# Memory.net
KiCad netlist of a schematic drawn in Altium Designer
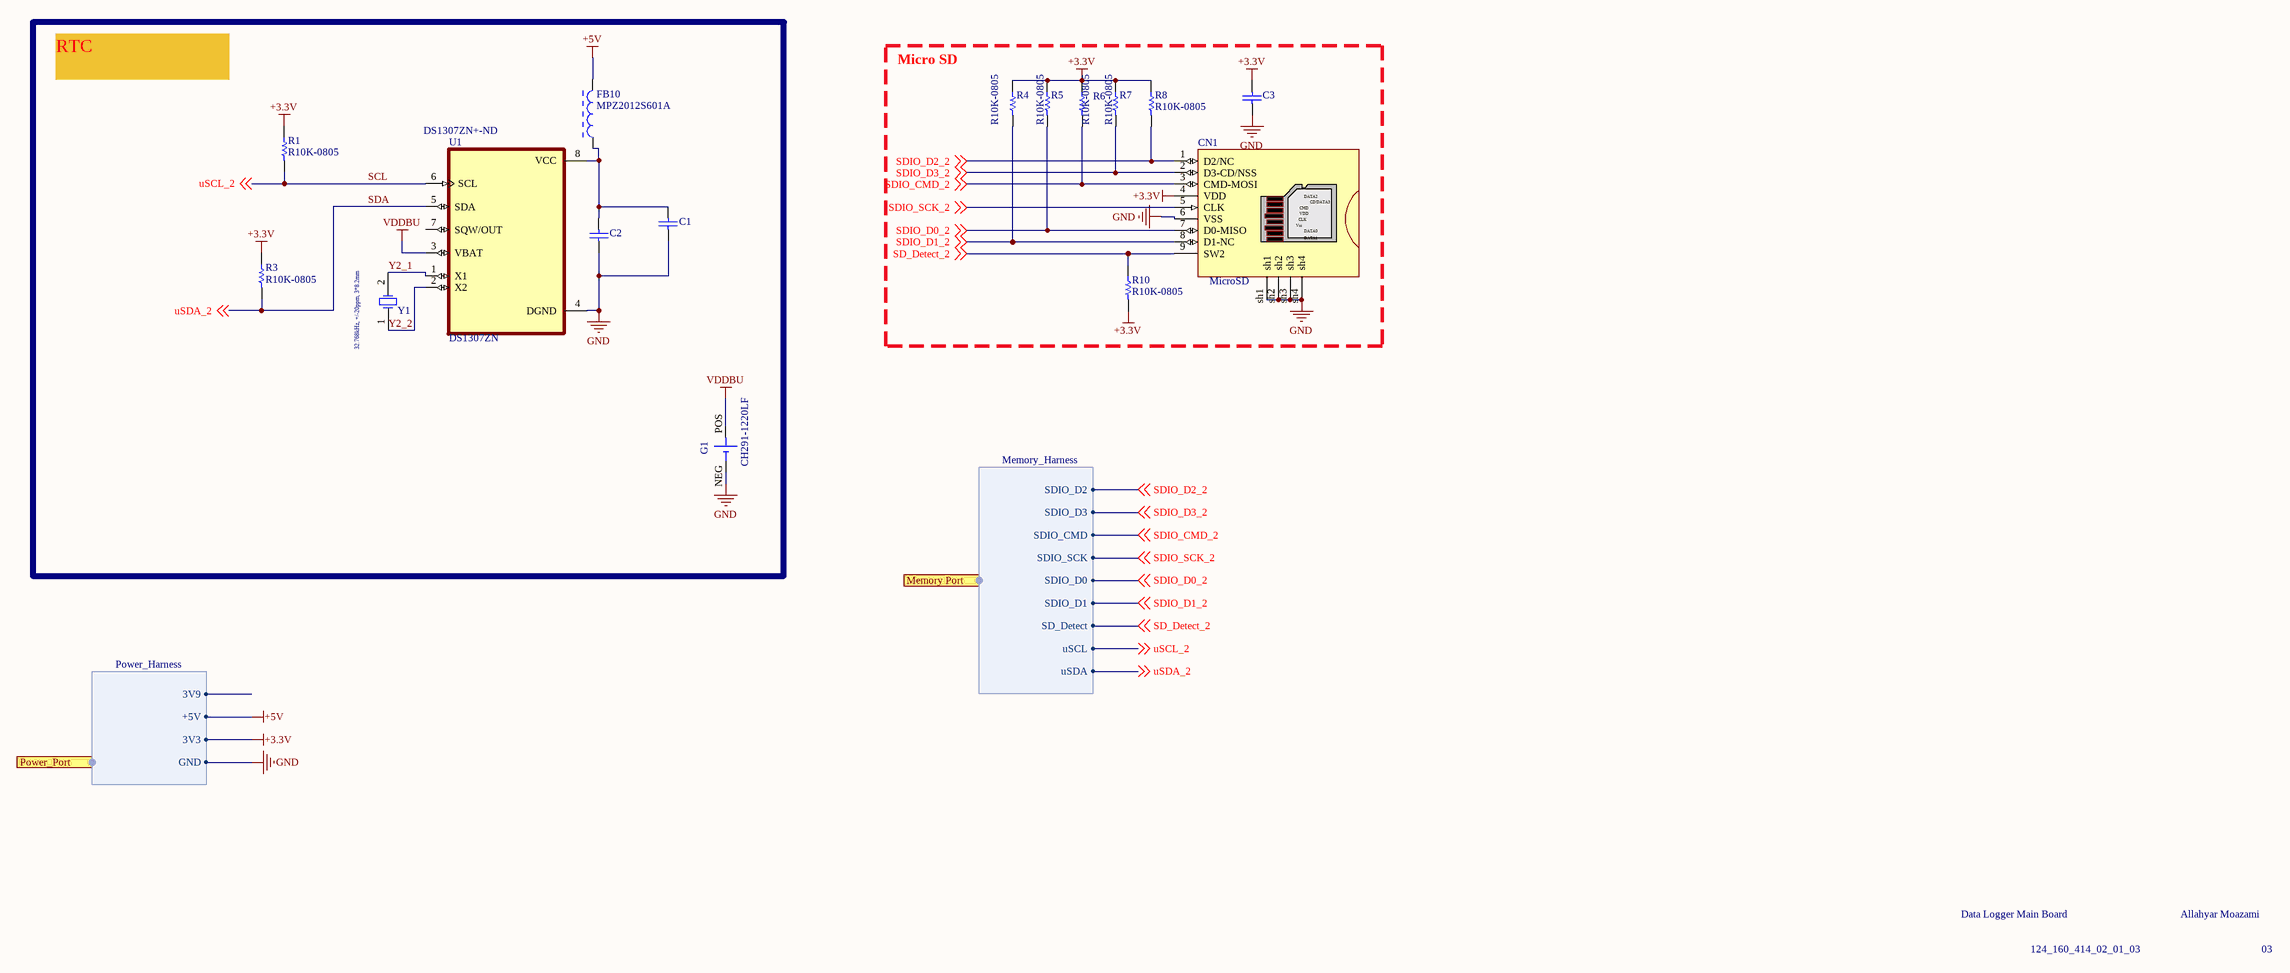
[diagram p0: Memory.SchDoc]

(export (version "E")
  (design (tool "Eeschema 10.0.6"))
  (components
    (comp (ref "C1")
      (value "~")
      (footprint "CRF06031")
      (description "Capacitor")
      (fields (field (name "DIGI-KEY_PART_NUMBER") "490-4789-1-ND"))
      (libsource (lib "Miscellaneous Devices") (part "Cap"))
    )
    (comp (ref "C2")
      (value "C100nF-0805")
      (footprint "CRF06031")
      (description "Capacitor")
      (fields (field (name "DIGI-KEY_PART_NUMBER") "490-4789-1-ND"))
      (libsource (lib "Miscellaneous Devices") (part "Cap"))
    )
    (comp (ref "C3")
      (value "~")
      (footprint "CRF06031")
      (description "Capacitor")
      (fields (field (name "DIGI-KEY_PART_NUMBER") "490-4789-1-ND"))
      (libsource (lib "Miscellaneous Devices") (part "Cap"))
    )
    (comp (ref "CN1")
      (value "MicroSD")
      (footprint "MicroSD")
      (description "MicroSD,9 pin")
      (fields (field (name "DIGI-KEY_PART_NUMBER") "2223-MSD-4-ATR-ND"))
      (libsource (lib "HosseinLib") (part "MicroSD"))
    )
    (comp (ref "FB10")
      (value "MPZ2012S601A")
      (footprint "TDK-MPZ2012_V")
      (fields (field (name "DIGI-KEY_PART_NUMBER") "445-MPZ2012S601AT000TR-ND"))
      (libsource (lib "Altium Content Vault") (part "BEAD-2"))
    )
    (comp (ref "G1")
      (value "CH291-1220LF")
      (footprint "*CH291-1220LF_CH291-1220LF(Primary)")
      (fields (field (name "MF") "Multicomp") (field (name "DIGI-KEY_PART_NUMBER") "952-1745-2-ND"))
      (libsource (lib "pH_rev3") (part "CH291-1220LF"))
    )
    (comp (ref "R1")
      (value "R10K-0805")
      (footprint "CRF06031")
      (description "Resistor")
      (fields (field (name "DIGI-KEY_PART_NUMBER") "13-RC0805FR-1310KLTR-ND"))
      (libsource (lib "Miscellaneous Devices") (part "Res1"))
    )
    (comp (ref "R3")
      (value "R10K-0805")
      (footprint "CRF06031")
      (description "Resistor")
      (fields (field (name "DIGI-KEY_PART_NUMBER") "13-RC0805FR-1310KLTR-ND"))
      (libsource (lib "Miscellaneous Devices") (part "Res1"))
    )
    (comp (ref "R4")
      (value "R10K-0805")
      (footprint "CRF06031")
      (description "Resistor")
      (fields (field (name "DIGI-KEY_PART_NUMBER") "13-RC0805FR-1310KLTR-ND"))
      (libsource (lib "Miscellaneous Devices") (part "Res1"))
    )
    (comp (ref "R5")
      (value "R10K-0805")
      (footprint "CRF06031")
      (description "Resistor")
      (fields (field (name "DIGI-KEY_PART_NUMBER") "13-RC0805FR-1310KLTR-ND"))
      (libsource (lib "Miscellaneous Devices") (part "Res1"))
    )
    (comp (ref "R6")
      (value "R10K-0805")
      (footprint "CRF06031")
      (description "Resistor")
      (fields (field (name "DIGI-KEY_PART_NUMBER") "13-RC0805FR-1310KLTR-ND"))
      (libsource (lib "Miscellaneous Devices") (part "Res1"))
    )
    (comp (ref "R7")
      (value "R10K-0805")
      (footprint "CRF06031")
      (description "Resistor")
      (fields (field (name "DIGI-KEY_PART_NUMBER") "13-RC0805FR-1310KLTR-ND"))
      (libsource (lib "Miscellaneous Devices") (part "Res1"))
    )
    (comp (ref "R8")
      (value "R10K-0805")
      (footprint "CRF06031")
      (description "Resistor")
      (fields (field (name "DIGI-KEY_PART_NUMBER") "13-RC0805FR-1310KLTR-ND"))
      (libsource (lib "Miscellaneous Devices") (part "Res1"))
    )
    (comp (ref "R10")
      (value "R10K-0805")
      (footprint "CRF06031")
      (description "Resistor")
      (fields (field (name "DIGI-KEY_PART_NUMBER") "13-RC0805FR-1310KLTR-ND"))
      (libsource (lib "Miscellaneous Devices") (part "Res1"))
    )
    (comp (ref "U1")
      (value "DS1307ZN")
      (footprint "SOIC127P600X175-8N")
      (description "Real Time Clock _RTC_ IC Clock/Calendar 56B IÂ²C, 2-Wire Serial 8-SOIC _0.154, 3.90mm Width_")
      (fields
        (field (name "MP") "DS1307ZN+")
        (field (name "MF") "Maxim Integrated")
        (field (name "SUPPLIER PART NUMBER 1") "DS1307ZN+-ND")
      )
      (libsource (lib "DS1307ZN") (part "DS1307ZN"))
    )
    (comp (ref "Y1")
      (value "32.768kHz, +/-20ppm, 3*8.2mm")
      (footprint "WE-XTAL_WATCH_3x8.2")
      (description "dip")
      (fields (field (name "PART NUMBER") "830002995B") (field (name "DIGI-KEY_PART_NUMBER") "XC2121-ND"))
      (libsource (lib "pH_rev3") (part "830002995B"))
    )
  )
  (nets
    (net (code "3") (name "+3.3V") (class "Default")
      (node (ref "C3") (pin "2") (pinfunction "2_2") (pintype "passive"))
      (node (ref "CN1") (pin "4") (pinfunction "VDD_4") (pintype "power_in"))
      (node (ref "R1") (pin "1") (pinfunction "1_1") (pintype "passive"))
      (node (ref "R10") (pin "2") (pinfunction "2_2") (pintype "passive"))
      (node (ref "R3") (pin "1") (pinfunction "1_1") (pintype "passive"))
      (node (ref "R4") (pin "1") (pinfunction "1_1") (pintype "passive"))
      (node (ref "R5") (pin "1") (pinfunction "1_1") (pintype "passive"))
      (node (ref "R6") (pin "1") (pinfunction "1_1") (pintype "passive"))
      (node (ref "R7") (pin "1") (pinfunction "1_1") (pintype "passive"))
      (node (ref "R8") (pin "1") (pinfunction "1_1") (pintype "passive"))
    )
    (net (code "4") (name "+5V") (class "Default")
      (node (ref "FB10") (pin "2") (pinfunction "2_2") (pintype "passive"))
    )
    (net (code "5") (name "/Y2_1") (class "Default")
      (node (ref "U1") (pin "1") (pinfunction "X1_1") (pintype "bidirectional"))
      (node (ref "Y1") (pin "2") (pinfunction "OSC2_2") (pintype "passive"))
    )
    (net (code "6") (name "/Y2_2") (class "Default")
      (node (ref "U1") (pin "2") (pinfunction "X2_2") (pintype "bidirectional"))
      (node (ref "Y1") (pin "1") (pinfunction "OSC1_1") (pintype "passive"))
    )
    (net (code "9") (name "GND") (class "Default")
      (node (ref "C1") (pin "1") (pinfunction "1_1") (pintype "passive"))
      (node (ref "C2") (pin "1") (pinfunction "1_1") (pintype "passive"))
      (node (ref "C3") (pin "1") (pinfunction "1_1") (pintype "passive"))
      (node (ref "CN1") (pin "6") (pinfunction "VSS_6") (pintype "power_in"))
      (node (ref "CN1") (pin "sh1") (pinfunction "sh1_sh1") (pintype "passive"))
      (node (ref "CN1") (pin "sh2") (pinfunction "sh2_sh2") (pintype "passive"))
      (node (ref "CN1") (pin "sh3") (pinfunction "sh3_sh3") (pintype "passive"))
      (node (ref "CN1") (pin "sh4") (pinfunction "sh4_sh4") (pintype "passive"))
      (node (ref "G1") (pin "NEG") (pinfunction "NEG_NEG") (pintype "passive"))
      (node (ref "U1") (pin "4") (pinfunction "DGND_4") (pintype "power_in"))
    )
    (net (code "10") (name "Net-(U1-VCC)") (class "Default")
      (node (ref "C1") (pin "2") (pinfunction "2_2") (pintype "passive"))
      (node (ref "C2") (pin "2") (pinfunction "2_2") (pintype "passive"))
      (node (ref "FB10") (pin "1") (pinfunction "1_1") (pintype "passive"))
      (node (ref "U1") (pin "8") (pinfunction "VCC_8") (pintype "power_in"))
    )
    (net (code "11") (name "SDIO_CMD_2") (class "Default")
      (node (ref "CN1") (pin "3") (pinfunction "CMD-MOSI_3") (pintype "bidirectional"))
      (node (ref "R6") (pin "2") (pinfunction "2_2") (pintype "passive"))
    )
    (net (code "12") (name "SDIO_D0_2") (class "Default")
      (node (ref "CN1") (pin "7") (pinfunction "D0-MISO_7") (pintype "bidirectional"))
      (node (ref "R5") (pin "2") (pinfunction "2_2") (pintype "passive"))
    )
    (net (code "13") (name "SDIO_D1_2") (class "Default")
      (node (ref "CN1") (pin "8") (pinfunction "D1-NC_8") (pintype "bidirectional"))
      (node (ref "R4") (pin "2") (pinfunction "2_2") (pintype "passive"))
    )
    (net (code "14") (name "SDIO_D2_2") (class "Default")
      (node (ref "CN1") (pin "1") (pinfunction "D2/NC_1") (pintype "bidirectional"))
      (node (ref "R8") (pin "2") (pinfunction "2_2") (pintype "passive"))
    )
    (net (code "15") (name "SDIO_D3_2") (class "Default")
      (node (ref "CN1") (pin "2") (pinfunction "D3-CD/NSS_2") (pintype "bidirectional"))
      (node (ref "R7") (pin "2") (pinfunction "2_2") (pintype "passive"))
    )
    (net (code "16") (name "SDIO_SCK_2") (class "Default")
      (node (ref "CN1") (pin "5") (pinfunction "CLK_5") (pintype "input"))
    )
    (net (code "17") (name "SD_Detect_2") (class "Default")
      (node (ref "CN1") (pin "9") (pinfunction "SW2_9") (pintype "passive"))
      (node (ref "R10") (pin "1") (pinfunction "1_1") (pintype "passive"))
    )
    (net (code "18") (name "VDDBU") (class "Default")
      (node (ref "G1") (pin "POS") (pinfunction "POS_POS") (pintype "passive"))
      (node (ref "U1") (pin "3") (pinfunction "VBAT_3") (pintype "bidirectional"))
    )
    (net (code "19") (name "uSCL_2") (class "Default")
      (node (ref "R1") (pin "2") (pinfunction "2_2") (pintype "passive"))
      (node (ref "U1") (pin "6") (pinfunction "SCL_6") (pintype "input"))
    )
    (net (code "20") (name "uSDA_2") (class "Default")
      (node (ref "R3") (pin "2") (pinfunction "2_2") (pintype "passive"))
      (node (ref "U1") (pin "5") (pinfunction "SDA_5") (pintype "bidirectional"))
    )
    (net (code "21") (name "unconnected-(U1-SQW{slash}OUT-Pad7)") (class "Default")
      (node (ref "U1") (pin "7") (pinfunction "SQW/OUT_7") (pintype "bidirectional"))
    )
  )
)
